# EMP11.net
KiCad netlist of a schematic drawn in EAGLE
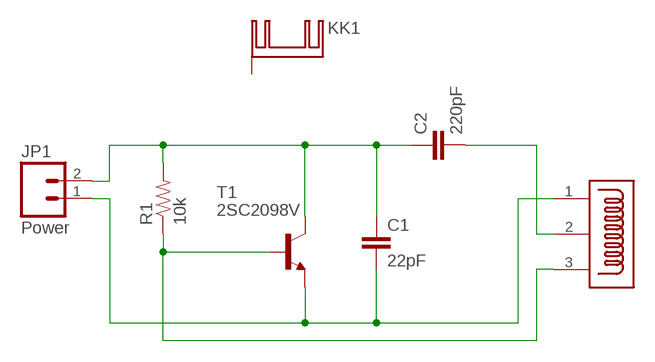
[diagram p0: schematic, sheet 1]

(export (version "E")
  (design (tool "Eeschema 10.0.6"))
  (components
    (comp (ref "C1")
      (value "22pF")
      (footprint "eagle-import:CAP-PTH-SMALL")
      (libsource (lib "eagle-import") (part "CAPPTH"))
    )
    (comp (ref "C2")
      (value "220pF")
      (footprint "eagle-import:CAP-PTH-SMALL")
      (libsource (lib "eagle-import") (part "CAPPTH"))
    )
    (comp (ref "JP1")
      (value "Power")
      (footprint "eagle-import:1X02")
      (libsource (lib "eagle-import") (part "M02PTH"))
    )
    (comp (ref "KK1")
      (value "D03PA-PAD")
      (footprint "eagle-import:D03PA-PAD")
      (libsource (lib "eagle-import") (part "D03PA-PAD"))
    )
    (comp (ref "R1")
      (value "10k")
      (footprint "eagle-import:AXIAL-0.4")
      (libsource (lib "eagle-import") (part "RESISTORPTH-1/4W"))
    )
    (comp (ref "T1")
      (value "2SC2098V")
      (footprint "eagle-import:TO220AV")
      (libsource (lib "eagle-import") (part "2SC2098V"))
    )
    (comp (ref "U$1")
      (value "EMP_WIRE")
      (footprint "eagle-import:EMP_WIRE")
      (libsource (lib "eagle-import") (part "EMP_WIRE"))
    )
  )
  (nets
    (net (code "1") (name "Net-(C2-Pad2)") (class "Default")
      (node (ref "C2") (pin "2") (pinfunction "2_2") (pintype "passive"))
      (node (ref "U$1") (pin "2") (pinfunction "2_2") (pintype "bidirectional"))
    )
    (net (code "2") (name "Net-(R1-1)") (class "Default")
      (node (ref "R1") (pin "P$1") (pinfunction "1_P$1") (pintype "passive"))
      (node (ref "T1") (pin "1") (pinfunction "B_1") (pintype "passive"))
      (node (ref "U$1") (pin "3") (pinfunction "3_3") (pintype "bidirectional"))
    )
    (net (code "3") (name "Net-(R1-2)") (class "Default")
      (node (ref "C1") (pin "1") (pinfunction "1_1") (pintype "passive"))
      (node (ref "C2") (pin "1") (pinfunction "1_1") (pintype "passive"))
      (node (ref "JP1") (pin "2") (pinfunction "2_2") (pintype "passive"))
      (node (ref "R1") (pin "P$2") (pinfunction "2_P$2") (pintype "passive"))
      (node (ref "T1") (pin "2") (pinfunction "C_2") (pintype "passive"))
    )
    (net (code "4") (name "Net-(T1-E)") (class "Default")
      (node (ref "C1") (pin "2") (pinfunction "2_2") (pintype "passive"))
      (node (ref "JP1") (pin "1") (pinfunction "1_1") (pintype "passive"))
      (node (ref "T1") (pin "3") (pinfunction "E_3") (pintype "passive"))
      (node (ref "U$1") (pin "1") (pinfunction "1_1") (pintype "bidirectional"))
    )
    (net (code "5") (name "unconnected-(KK1-K-PadB)") (class "Default")
      (node (ref "KK1") (pin "B") (pinfunction "K_B") (pintype "passive"))
    )
  )
)
